# OECU_BASE4.net
KiCad netlist of a schematic drawn in Altium Designer
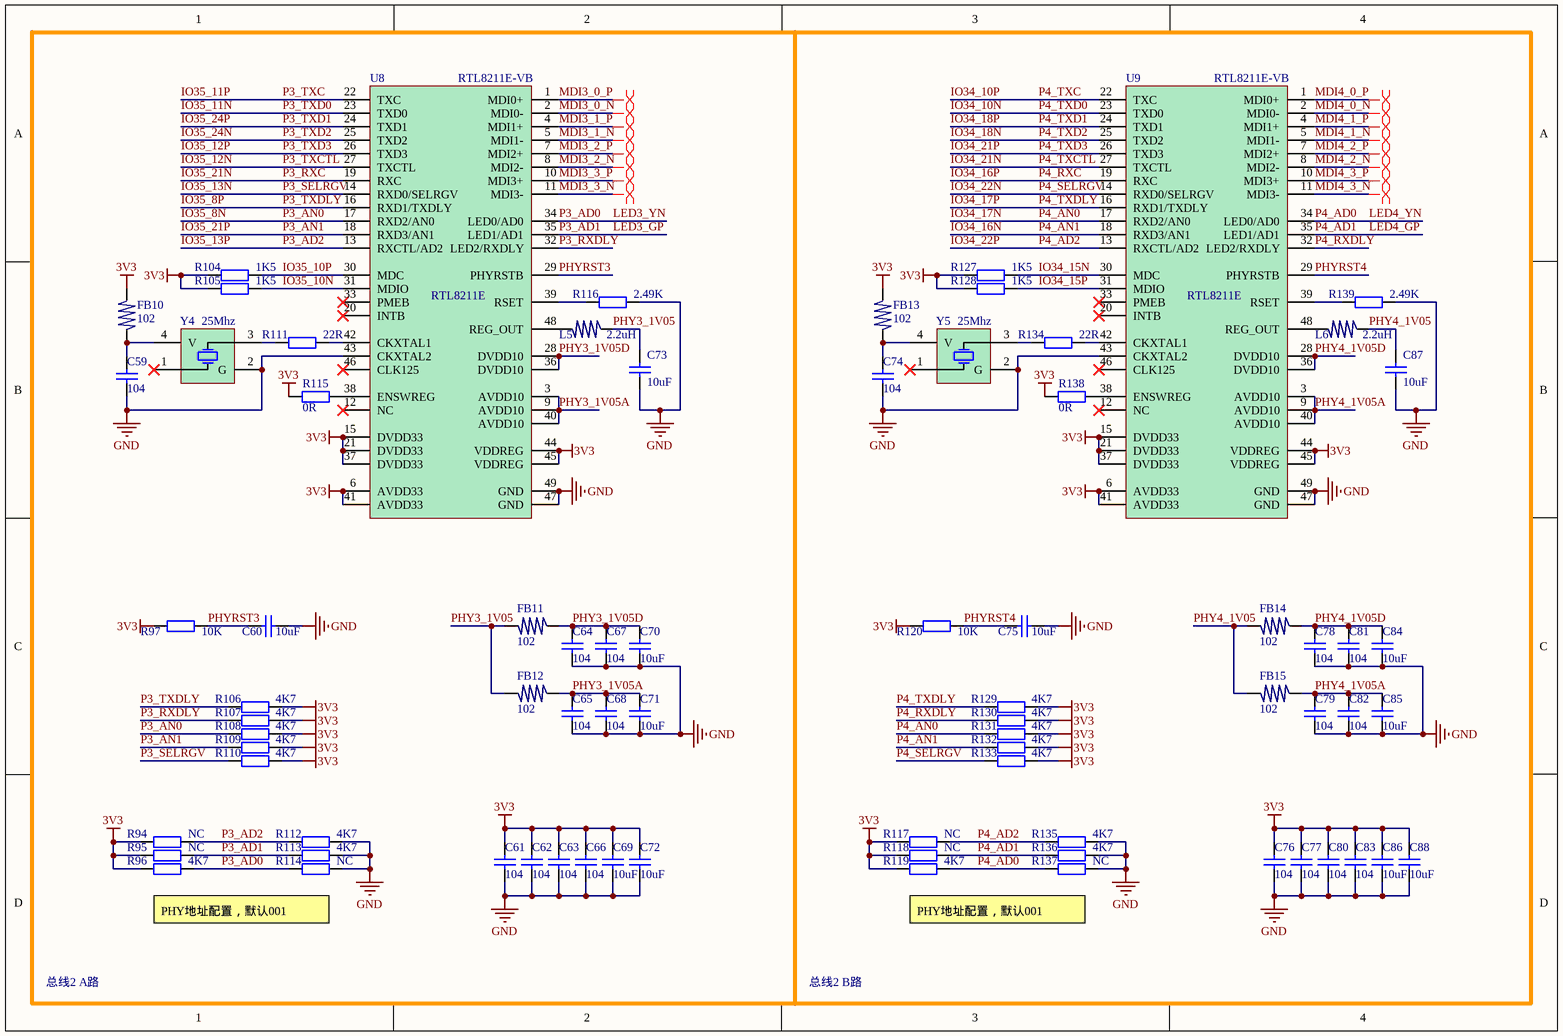
[diagram p0: OECU_BASE4.SchDoc]

(export (version "E")
  (design (tool "Eeschema 10.0.6"))
  (components
    (comp (ref "C59")
      (value "104")
      (footprint "0402")
      (description "贴片电容 0402")
      (libsource (lib "MT_Device") (part "CAP_0402"))
    )
    (comp (ref "C60")
      (value "10uF")
      (footprint "0402")
      (description "贴片电容 0402")
      (libsource (lib "MT_Device") (part "CAP_0402"))
    )
    (comp (ref "C61")
      (value "104")
      (footprint "0402")
      (description "贴片电容 0402")
      (libsource (lib "MT_Device") (part "CAP_0402"))
    )
    (comp (ref "C62")
      (value "104")
      (footprint "0402")
      (description "贴片电容 0402")
      (libsource (lib "MT_Device") (part "CAP_0402"))
    )
    (comp (ref "C63")
      (value "104")
      (footprint "0402")
      (description "贴片电容 0402")
      (libsource (lib "MT_Device") (part "CAP_0402"))
    )
    (comp (ref "C64")
      (value "104")
      (footprint "0402")
      (description "贴片电容 0402")
      (libsource (lib "MT_Device") (part "CAP_0402"))
    )
    (comp (ref "C65")
      (value "104")
      (footprint "0402")
      (description "贴片电容 0402")
      (libsource (lib "MT_Device") (part "CAP_0402"))
    )
    (comp (ref "C66")
      (value "104")
      (footprint "0402")
      (description "贴片电容 0402")
      (libsource (lib "MT_Device") (part "CAP_0402"))
    )
    (comp (ref "C67")
      (value "104")
      (footprint "0402")
      (description "贴片电容 0402")
      (libsource (lib "MT_Device") (part "CAP_0402"))
    )
    (comp (ref "C68")
      (value "104")
      (footprint "0402")
      (description "贴片电容 0402")
      (libsource (lib "MT_Device") (part "CAP_0402"))
    )
    (comp (ref "C69")
      (value "10uF")
      (footprint "0402")
      (description "贴片电容 0402")
      (libsource (lib "MT_Device") (part "CAP_0402"))
    )
    (comp (ref "C70")
      (value "10uF")
      (footprint "0402")
      (description "贴片电容 0402")
      (libsource (lib "MT_Device") (part "CAP_0402"))
    )
    (comp (ref "C71")
      (value "10uF")
      (footprint "0402")
      (description "贴片电容 0402")
      (libsource (lib "MT_Device") (part "CAP_0402"))
    )
    (comp (ref "C72")
      (value "10uF")
      (footprint "0402")
      (description "贴片电容 0402")
      (libsource (lib "MT_Device") (part "CAP_0402"))
    )
    (comp (ref "C73")
      (value "10uF")
      (footprint "0402")
      (description "贴片电容 0402")
      (libsource (lib "MT_Device") (part "CAP_0402"))
    )
    (comp (ref "C74")
      (value "104")
      (footprint "0402")
      (description "贴片电容 0402")
      (libsource (lib "MT_Device") (part "CAP_0402"))
    )
    (comp (ref "C75")
      (value "10uF")
      (footprint "0402")
      (description "贴片电容 0402")
      (libsource (lib "MT_Device") (part "CAP_0402"))
    )
    (comp (ref "C76")
      (value "104")
      (footprint "0402")
      (description "贴片电容 0402")
      (libsource (lib "MT_Device") (part "CAP_0402"))
    )
    (comp (ref "C77")
      (value "104")
      (footprint "0402")
      (description "贴片电容 0402")
      (libsource (lib "MT_Device") (part "CAP_0402"))
    )
    (comp (ref "C78")
      (value "104")
      (footprint "0402")
      (description "贴片电容 0402")
      (libsource (lib "MT_Device") (part "CAP_0402"))
    )
    (comp (ref "C79")
      (value "104")
      (footprint "0402")
      (description "贴片电容 0402")
      (libsource (lib "MT_Device") (part "CAP_0402"))
    )
    (comp (ref "C80")
      (value "104")
      (footprint "0402")
      (description "贴片电容 0402")
      (libsource (lib "MT_Device") (part "CAP_0402"))
    )
    (comp (ref "C81")
      (value "104")
      (footprint "0402")
      (description "贴片电容 0402")
      (libsource (lib "MT_Device") (part "CAP_0402"))
    )
    (comp (ref "C82")
      (value "104")
      (footprint "0402")
      (description "贴片电容 0402")
      (libsource (lib "MT_Device") (part "CAP_0402"))
    )
    (comp (ref "C83")
      (value "104")
      (footprint "0402")
      (description "贴片电容 0402")
      (libsource (lib "MT_Device") (part "CAP_0402"))
    )
    (comp (ref "C84")
      (value "10uF")
      (footprint "0402")
      (description "贴片电容 0402")
      (libsource (lib "MT_Device") (part "CAP_0402"))
    )
    (comp (ref "C85")
      (value "10uF")
      (footprint "0402")
      (description "贴片电容 0402")
      (libsource (lib "MT_Device") (part "CAP_0402"))
    )
    (comp (ref "C86")
      (value "10uF")
      (footprint "0402")
      (description "贴片电容 0402")
      (libsource (lib "MT_Device") (part "CAP_0402"))
    )
    (comp (ref "C87")
      (value "10uF")
      (footprint "0402")
      (description "贴片电容 0402")
      (libsource (lib "MT_Device") (part "CAP_0402"))
    )
    (comp (ref "C88")
      (value "10uF")
      (footprint "0402")
      (description "贴片电容 0402")
      (libsource (lib "MT_Device") (part "CAP_0402"))
    )
    (comp (ref "FB10")
      (value "102")
      (footprint "0402")
      (description "磁珠 0402")
      (libsource (lib "MT_Device") (part "FB_0402"))
    )
    (comp (ref "FB11")
      (value "102")
      (footprint "0603")
      (description "磁珠 0603")
      (libsource (lib "MT_Device") (part "FB_0603"))
    )
    (comp (ref "FB12")
      (value "102")
      (footprint "0603")
      (description "磁珠 0603")
      (libsource (lib "MT_Device") (part "FB_0603"))
    )
    (comp (ref "FB13")
      (value "102")
      (footprint "0402")
      (description "磁珠 0402")
      (libsource (lib "MT_Device") (part "FB_0402"))
    )
    (comp (ref "FB14")
      (value "102")
      (footprint "0603")
      (description "磁珠 0603")
      (libsource (lib "MT_Device") (part "FB_0603"))
    )
    (comp (ref "FB15")
      (value "102")
      (footprint "0603")
      (description "磁珠 0603")
      (libsource (lib "MT_Device") (part "FB_0603"))
    )
    (comp (ref "L5")
      (value "2.2uH")
      (footprint "0805")
      (description "电感 0805")
      (libsource (lib "MT_Device") (part "L_0805"))
    )
    (comp (ref "L6")
      (value "2.2uH")
      (footprint "0805")
      (description "电感 0805")
      (libsource (lib "MT_Device") (part "L_0805"))
    )
    (comp (ref "R94")
      (value "NC")
      (footprint "R_0402")
      (description "电阻 0402")
      (libsource (lib "MT_Device") (part "RES_0402"))
    )
    (comp (ref "R95")
      (value "NC")
      (footprint "R_0402")
      (description "电阻 0402")
      (libsource (lib "MT_Device") (part "RES_0402"))
    )
    (comp (ref "R96")
      (value "4K7")
      (footprint "R_0402")
      (description "电阻 0402")
      (libsource (lib "MT_Device") (part "RES_0402"))
    )
    (comp (ref "R97")
      (value "10K")
      (footprint "R_0402")
      (description "电阻 0402")
      (libsource (lib "MT_Device") (part "RES_0402"))
    )
    (comp (ref "R104")
      (value "1K5")
      (footprint "R_0402")
      (description "电阻 0402")
      (libsource (lib "") (part "RES_0402_1"))
    )
    (comp (ref "R105")
      (value "1K5")
      (footprint "R_0402")
      (description "电阻 0402")
      (libsource (lib "") (part "RES_0402_1"))
    )
    (comp (ref "R106")
      (value "4K7")
      (footprint "R_0402")
      (description "电阻 0402")
      (libsource (lib "MT_Device") (part "RES_0402"))
    )
    (comp (ref "R107")
      (value "4K7")
      (footprint "R_0402")
      (description "电阻 0402")
      (libsource (lib "MT_Device") (part "RES_0402"))
    )
    (comp (ref "R108")
      (value "4K7")
      (footprint "R_0402")
      (description "电阻 0402")
      (libsource (lib "MT_Device") (part "RES_0402"))
    )
    (comp (ref "R109")
      (value "4K7")
      (footprint "R_0402")
      (description "电阻 0402")
      (libsource (lib "MT_Device") (part "RES_0402"))
    )
    (comp (ref "R110")
      (value "4K7")
      (footprint "R_0402")
      (description "电阻 0402")
      (libsource (lib "MT_Device") (part "RES_0402"))
    )
    (comp (ref "R111")
      (value "22R")
      (footprint "R_0402")
      (description "电阻 0402")
      (libsource (lib "") (part "RES_0402_1"))
    )
    (comp (ref "R112")
      (value "4K7")
      (footprint "R_0402")
      (description "电阻 0402")
      (libsource (lib "MT_Device") (part "RES_0402"))
    )
    (comp (ref "R113")
      (value "4K7")
      (footprint "R_0402")
      (description "电阻 0402")
      (libsource (lib "MT_Device") (part "RES_0402"))
    )
    (comp (ref "R114")
      (value "NC")
      (footprint "R_0402")
      (description "电阻 0402")
      (libsource (lib "MT_Device") (part "RES_0402"))
    )
    (comp (ref "R115")
      (value "0R")
      (footprint "R_0402")
      (description "电阻 0402")
      (libsource (lib "") (part "RES_0402_1"))
    )
    (comp (ref "R116")
      (value "2.49K")
      (footprint "R_0402")
      (description "电阻 0402")
      (libsource (lib "MT_Device") (part "RES_0402"))
    )
    (comp (ref "R117")
      (value "NC")
      (footprint "R_0402")
      (description "电阻 0402")
      (libsource (lib "MT_Device") (part "RES_0402"))
    )
    (comp (ref "R118")
      (value "NC")
      (footprint "R_0402")
      (description "电阻 0402")
      (libsource (lib "MT_Device") (part "RES_0402"))
    )
    (comp (ref "R119")
      (value "4K7")
      (footprint "R_0402")
      (description "电阻 0402")
      (libsource (lib "MT_Device") (part "RES_0402"))
    )
    (comp (ref "R120")
      (value "10K")
      (footprint "R_0402")
      (description "电阻 0402")
      (libsource (lib "MT_Device") (part "RES_0402"))
    )
    (comp (ref "R127")
      (value "1K5")
      (footprint "R_0402")
      (description "电阻 0402")
      (libsource (lib "") (part "RES_0402_1"))
    )
    (comp (ref "R128")
      (value "1K5")
      (footprint "R_0402")
      (description "电阻 0402")
      (libsource (lib "") (part "RES_0402_1"))
    )
    (comp (ref "R129")
      (value "4K7")
      (footprint "R_0402")
      (description "电阻 0402")
      (libsource (lib "MT_Device") (part "RES_0402"))
    )
    (comp (ref "R130")
      (value "4K7")
      (footprint "R_0402")
      (description "电阻 0402")
      (libsource (lib "MT_Device") (part "RES_0402"))
    )
    (comp (ref "R131")
      (value "4K7")
      (footprint "R_0402")
      (description "电阻 0402")
      (libsource (lib "MT_Device") (part "RES_0402"))
    )
    (comp (ref "R132")
      (value "4K7")
      (footprint "R_0402")
      (description "电阻 0402")
      (libsource (lib "MT_Device") (part "RES_0402"))
    )
    (comp (ref "R133")
      (value "4K7")
      (footprint "R_0402")
      (description "电阻 0402")
      (libsource (lib "MT_Device") (part "RES_0402"))
    )
    (comp (ref "R134")
      (value "22R")
      (footprint "R_0402")
      (description "电阻 0402")
      (libsource (lib "") (part "RES_0402_1"))
    )
    (comp (ref "R135")
      (value "4K7")
      (footprint "R_0402")
      (description "电阻 0402")
      (libsource (lib "MT_Device") (part "RES_0402"))
    )
    (comp (ref "R136")
      (value "4K7")
      (footprint "R_0402")
      (description "电阻 0402")
      (libsource (lib "MT_Device") (part "RES_0402"))
    )
    (comp (ref "R137")
      (value "NC")
      (footprint "R_0402")
      (description "电阻 0402")
      (libsource (lib "MT_Device") (part "RES_0402"))
    )
    (comp (ref "R138")
      (value "0R")
      (footprint "R_0402")
      (description "电阻 0402")
      (libsource (lib "") (part "RES_0402_1"))
    )
    (comp (ref "R139")
      (value "2.49K")
      (footprint "R_0402")
      (description "电阻 0402")
      (libsource (lib "MT_Device") (part "RES_0402"))
    )
    (comp (ref "U8")
      (value "RTL8211E-VB")
      (footprint "QFN48")
      (description "QFN48")
      (libsource (lib "MT_Chip") (part "RTL8211E"))
    )
    (comp (ref "U9")
      (value "RTL8211E-VB")
      (footprint "QFN48")
      (description "QFN48")
      (libsource (lib "MT_Chip") (part "RTL8211E"))
    )
    (comp (ref "Y4") (value "25Mhz") (footprint "XTAL_3225") (libsource (lib "MT_Device") (part "XTAL_3225")))
    (comp (ref "Y5") (value "25Mhz") (footprint "XTAL_3225") (libsource (lib "MT_Device") (part "XTAL_3225")))
  )
  (nets
    (net (code "1") (name "/IO34_10N") (class "Default")
      (node (ref "U9") (pin "23") (pinfunction "TXD0_23") (pintype "passive"))
    )
    (net (code "2") (name "/IO34_10P") (class "Default")
      (node (ref "U9") (pin "22") (pinfunction "TXC_22") (pintype "passive"))
    )
    (net (code "3") (name "/IO34_15N") (class "Default")
      (node (ref "R127") (pin "1") (pinfunction "1_1") (pintype "passive"))
      (node (ref "U9") (pin "30") (pinfunction "MDC_30") (pintype "passive"))
    )
    (net (code "4") (name "/IO34_15P") (class "Default")
      (node (ref "R128") (pin "1") (pinfunction "1_1") (pintype "passive"))
      (node (ref "U9") (pin "31") (pinfunction "MDIO_31") (pintype "passive"))
    )
    (net (code "5") (name "/IO34_16N") (class "Default")
      (node (ref "R132") (pin "1") (pinfunction "1_1") (pintype "passive"))
      (node (ref "U9") (pin "18") (pinfunction "RXD3/AN1_18") (pintype "passive"))
    )
    (net (code "6") (name "/IO34_16P") (class "Default")
      (node (ref "U9") (pin "19") (pinfunction "RXC_19") (pintype "passive"))
    )
    (net (code "7") (name "/IO34_17N") (class "Default")
      (node (ref "R131") (pin "1") (pinfunction "1_1") (pintype "passive"))
      (node (ref "U9") (pin "17") (pinfunction "RXD2/AN0_17") (pintype "passive"))
    )
    (net (code "8") (name "/IO34_17P") (class "Default")
      (node (ref "R129") (pin "1") (pinfunction "1_1") (pintype "passive"))
      (node (ref "U9") (pin "16") (pinfunction "RXD1/TXDLY_16") (pintype "passive"))
    )
    (net (code "9") (name "/IO34_18N") (class "Default")
      (node (ref "U9") (pin "25") (pinfunction "TXD2_25") (pintype "passive"))
    )
    (net (code "10") (name "/IO34_18P") (class "Default")
      (node (ref "U9") (pin "24") (pinfunction "TXD1_24") (pintype "passive"))
    )
    (net (code "11") (name "/IO34_21N") (class "Default")
      (node (ref "U9") (pin "27") (pinfunction "TXCTL_27") (pintype "passive"))
    )
    (net (code "12") (name "/IO34_21P") (class "Default")
      (node (ref "U9") (pin "26") (pinfunction "TXD3_26") (pintype "passive"))
    )
    (net (code "13") (name "/IO34_22N") (class "Default")
      (node (ref "R133") (pin "1") (pinfunction "1_1") (pintype "passive"))
      (node (ref "U9") (pin "14") (pinfunction "RXD0/SELRGV_14") (pintype "passive"))
    )
    (net (code "14") (name "/IO34_22P") (class "Default")
      (node (ref "R117") (pin "2") (pinfunction "2_2") (pintype "passive"))
      (node (ref "R135") (pin "1") (pinfunction "1_1") (pintype "passive"))
      (node (ref "U9") (pin "13") (pinfunction "RXCTL/AD2_13") (pintype "passive"))
    )
    (net (code "15") (name "/IO35_8N") (class "Default")
      (node (ref "R108") (pin "1") (pinfunction "1_1") (pintype "passive"))
      (node (ref "U8") (pin "17") (pinfunction "RXD2/AN0_17") (pintype "passive"))
    )
    (net (code "16") (name "/IO35_8P") (class "Default")
      (node (ref "R106") (pin "1") (pinfunction "1_1") (pintype "passive"))
      (node (ref "U8") (pin "16") (pinfunction "RXD1/TXDLY_16") (pintype "passive"))
    )
    (net (code "17") (name "/IO35_10N") (class "Default")
      (node (ref "R105") (pin "1") (pinfunction "1_1") (pintype "passive"))
      (node (ref "U8") (pin "31") (pinfunction "MDIO_31") (pintype "passive"))
    )
    (net (code "18") (name "/IO35_10P") (class "Default")
      (node (ref "R104") (pin "1") (pinfunction "1_1") (pintype "passive"))
      (node (ref "U8") (pin "30") (pinfunction "MDC_30") (pintype "passive"))
    )
    (net (code "19") (name "/IO35_11N") (class "Default")
      (node (ref "U8") (pin "23") (pinfunction "TXD0_23") (pintype "passive"))
    )
    (net (code "20") (name "/IO35_11P") (class "Default")
      (node (ref "U8") (pin "22") (pinfunction "TXC_22") (pintype "passive"))
    )
    (net (code "21") (name "/IO35_12N") (class "Default")
      (node (ref "U8") (pin "27") (pinfunction "TXCTL_27") (pintype "passive"))
    )
    (net (code "22") (name "/IO35_12P") (class "Default")
      (node (ref "U8") (pin "26") (pinfunction "TXD3_26") (pintype "passive"))
    )
    (net (code "23") (name "/IO35_13N") (class "Default")
      (node (ref "R110") (pin "1") (pinfunction "1_1") (pintype "passive"))
      (node (ref "U8") (pin "14") (pinfunction "RXD0/SELRGV_14") (pintype "passive"))
    )
    (net (code "24") (name "/IO35_13P") (class "Default")
      (node (ref "R112") (pin "1") (pinfunction "1_1") (pintype "passive"))
      (node (ref "R94") (pin "2") (pinfunction "2_2") (pintype "passive"))
      (node (ref "U8") (pin "13") (pinfunction "RXCTL/AD2_13") (pintype "passive"))
    )
    (net (code "25") (name "/IO35_21N") (class "Default")
      (node (ref "U8") (pin "19") (pinfunction "RXC_19") (pintype "passive"))
    )
    (net (code "26") (name "/IO35_21P") (class "Default")
      (node (ref "R109") (pin "1") (pinfunction "1_1") (pintype "passive"))
      (node (ref "U8") (pin "18") (pinfunction "RXD3/AN1_18") (pintype "passive"))
    )
    (net (code "27") (name "/IO35_24N") (class "Default")
      (node (ref "U8") (pin "25") (pinfunction "TXD2_25") (pintype "passive"))
    )
    (net (code "28") (name "/IO35_24P") (class "Default")
      (node (ref "U8") (pin "24") (pinfunction "TXD1_24") (pintype "passive"))
    )
    (net (code "29") (name "/LED3_GP") (class "Default")
      (node (ref "R113") (pin "1") (pinfunction "1_1") (pintype "passive"))
      (node (ref "R95") (pin "2") (pinfunction "2_2") (pintype "passive"))
      (node (ref "U8") (pin "35") (pinfunction "LED1/AD1_35") (pintype "passive"))
    )
    (net (code "30") (name "/LED3_YN") (class "Default")
      (node (ref "R114") (pin "1") (pinfunction "1_1") (pintype "passive"))
      (node (ref "R96") (pin "2") (pinfunction "2_2") (pintype "passive"))
      (node (ref "U8") (pin "34") (pinfunction "LED0/AD0_34") (pintype "passive"))
    )
    (net (code "31") (name "/LED4_GP") (class "Default")
      (node (ref "R118") (pin "2") (pinfunction "2_2") (pintype "passive"))
      (node (ref "R136") (pin "1") (pinfunction "1_1") (pintype "passive"))
      (node (ref "U9") (pin "35") (pinfunction "LED1/AD1_35") (pintype "passive"))
    )
    (net (code "32") (name "/LED4_YN") (class "Default")
      (node (ref "R119") (pin "2") (pinfunction "2_2") (pintype "passive"))
      (node (ref "R137") (pin "1") (pinfunction "1_1") (pintype "passive"))
      (node (ref "U9") (pin "34") (pinfunction "LED0/AD0_34") (pintype "passive"))
    )
    (net (code "33") (name "/MDI3_0_N") (class "Default")
      (node (ref "U8") (pin "2") (pinfunction "MDI0-_2") (pintype "passive"))
    )
    (net (code "34") (name "/MDI3_0_P") (class "Default")
      (node (ref "U8") (pin "1") (pinfunction "MDI0+_1") (pintype "passive"))
    )
    (net (code "35") (name "/MDI3_1_N") (class "Default")
      (node (ref "U8") (pin "5") (pinfunction "MDI1-_5") (pintype "passive"))
    )
    (net (code "36") (name "/MDI3_1_P") (class "Default")
      (node (ref "U8") (pin "4") (pinfunction "MDI1+_4") (pintype "passive"))
    )
    (net (code "37") (name "/MDI3_2_N") (class "Default")
      (node (ref "U8") (pin "8") (pinfunction "MDI2-_8") (pintype "passive"))
    )
    (net (code "38") (name "/MDI3_2_P") (class "Default")
      (node (ref "U8") (pin "7") (pinfunction "MDI2+_7") (pintype "passive"))
    )
    (net (code "39") (name "/MDI3_3_N") (class "Default")
      (node (ref "U8") (pin "11") (pinfunction "MDI3-_11") (pintype "passive"))
    )
    (net (code "40") (name "/MDI3_3_P") (class "Default")
      (node (ref "U8") (pin "10") (pinfunction "MDI3+_10") (pintype "passive"))
    )
    (net (code "41") (name "/MDI4_0_N") (class "Default")
      (node (ref "U9") (pin "2") (pinfunction "MDI0-_2") (pintype "passive"))
    )
    (net (code "42") (name "/MDI4_0_P") (class "Default")
      (node (ref "U9") (pin "1") (pinfunction "MDI0+_1") (pintype "passive"))
    )
    (net (code "43") (name "/MDI4_1_N") (class "Default")
      (node (ref "U9") (pin "5") (pinfunction "MDI1-_5") (pintype "passive"))
    )
    (net (code "44") (name "/MDI4_1_P") (class "Default")
      (node (ref "U9") (pin "4") (pinfunction "MDI1+_4") (pintype "passive"))
    )
    (net (code "45") (name "/MDI4_2_N") (class "Default")
      (node (ref "U9") (pin "8") (pinfunction "MDI2-_8") (pintype "passive"))
    )
    (net (code "46") (name "/MDI4_2_P") (class "Default")
      (node (ref "U9") (pin "7") (pinfunction "MDI2+_7") (pintype "passive"))
    )
    (net (code "47") (name "/MDI4_3_N") (class "Default")
      (node (ref "U9") (pin "11") (pinfunction "MDI3-_11") (pintype "passive"))
    )
    (net (code "48") (name "/MDI4_3_P") (class "Default")
      (node (ref "U9") (pin "10") (pinfunction "MDI3+_10") (pintype "passive"))
    )
    (net (code "49") (name "/P3_RXDLY") (class "Default")
      (node (ref "R107") (pin "1") (pinfunction "1_1") (pintype "passive"))
      (node (ref "U8") (pin "32") (pinfunction "LED2/RXDLY_32") (pintype "passive"))
    )
    (net (code "50") (name "/P4_RXDLY") (class "Default")
      (node (ref "R130") (pin "1") (pinfunction "1_1") (pintype "passive"))
      (node (ref "U9") (pin "32") (pinfunction "LED2/RXDLY_32") (pintype "passive"))
    )
    (net (code "51") (name "/PHY3_1V05") (class "Default")
      (node (ref "C73") (pin "2") (pinfunction "2_2") (pintype "passive"))
      (node (ref "FB11") (pin "1") (pintype "passive"))
      (node (ref "FB12") (pin "1") (pintype "passive"))
      (node (ref "L5") (pin "1") (pintype "passive"))
    )
    (net (code "52") (name "/PHY3_1V05A") (class "Default")
      (node (ref "C65") (pin "2") (pinfunction "2_2") (pintype "passive"))
      (node (ref "C68") (pin "2") (pinfunction "2_2") (pintype "passive"))
      (node (ref "C71") (pin "2") (pinfunction "2_2") (pintype "passive"))
      (node (ref "FB12") (pin "2") (pintype "passive"))
      (node (ref "U8") (pin "3") (pinfunction "AVDD10_3") (pintype "passive"))
      (node (ref "U8") (pin "40") (pinfunction "AVDD10_40") (pintype "passive"))
      (node (ref "U8") (pin "9") (pinfunction "AVDD10_9") (pintype "passive"))
    )
    (net (code "53") (name "/PHY3_1V05D") (class "Default")
      (node (ref "C64") (pin "2") (pinfunction "2_2") (pintype "passive"))
      (node (ref "C67") (pin "2") (pinfunction "2_2") (pintype "passive"))
      (node (ref "C70") (pin "2") (pinfunction "2_2") (pintype "passive"))
      (node (ref "FB11") (pin "2") (pintype "passive"))
      (node (ref "U8") (pin "28") (pinfunction "DVDD10_28") (pintype "passive"))
      (node (ref "U8") (pin "36") (pinfunction "DVDD10_36") (pintype "passive"))
    )
    (net (code "54") (name "/PHY4_1V05") (class "Default")
      (node (ref "C87") (pin "2") (pinfunction "2_2") (pintype "passive"))
      (node (ref "FB14") (pin "1") (pintype "passive"))
      (node (ref "FB15") (pin "1") (pintype "passive"))
      (node (ref "L6") (pin "1") (pintype "passive"))
    )
    (net (code "55") (name "/PHY4_1V05A") (class "Default")
      (node (ref "C79") (pin "2") (pinfunction "2_2") (pintype "passive"))
      (node (ref "C82") (pin "2") (pinfunction "2_2") (pintype "passive"))
      (node (ref "C85") (pin "2") (pinfunction "2_2") (pintype "passive"))
      (node (ref "FB15") (pin "2") (pintype "passive"))
      (node (ref "U9") (pin "3") (pinfunction "AVDD10_3") (pintype "passive"))
      (node (ref "U9") (pin "40") (pinfunction "AVDD10_40") (pintype "passive"))
      (node (ref "U9") (pin "9") (pinfunction "AVDD10_9") (pintype "passive"))
    )
    (net (code "56") (name "/PHY4_1V05D") (class "Default")
      (node (ref "C78") (pin "2") (pinfunction "2_2") (pintype "passive"))
      (node (ref "C81") (pin "2") (pinfunction "2_2") (pintype "passive"))
      (node (ref "C84") (pin "2") (pinfunction "2_2") (pintype "passive"))
      (node (ref "FB14") (pin "2") (pintype "passive"))
      (node (ref "U9") (pin "28") (pinfunction "DVDD10_28") (pintype "passive"))
      (node (ref "U9") (pin "36") (pinfunction "DVDD10_36") (pintype "passive"))
    )
    (net (code "57") (name "/PHYRST3") (class "Default")
      (node (ref "C60") (pin "1") (pinfunction "1_1") (pintype "passive"))
      (node (ref "R97") (pin "2") (pinfunction "2_2") (pintype "passive"))
      (node (ref "U8") (pin "29") (pinfunction "PHYRSTB_29") (pintype "passive"))
    )
    (net (code "58") (name "/PHYRST4") (class "Default")
      (node (ref "C75") (pin "1") (pinfunction "1_1") (pintype "passive"))
      (node (ref "R120") (pin "2") (pinfunction "2_2") (pintype "passive"))
      (node (ref "U9") (pin "29") (pinfunction "PHYRSTB_29") (pintype "passive"))
    )
    (net (code "59") (name "3V3") (class "Default")
      (node (ref "C61") (pin "1") (pinfunction "1_1") (pintype "passive"))
      (node (ref "C62") (pin "1") (pinfunction "1_1") (pintype "passive"))
      (node (ref "C63") (pin "1") (pinfunction "1_1") (pintype "passive"))
      (node (ref "C66") (pin "1") (pinfunction "1_1") (pintype "passive"))
      (node (ref "C69") (pin "1") (pinfunction "1_1") (pintype "passive"))
      (node (ref "C72") (pin "1") (pinfunction "1_1") (pintype "passive"))
      (node (ref "C76") (pin "1") (pinfunction "1_1") (pintype "passive"))
      (node (ref "C77") (pin "1") (pinfunction "1_1") (pintype "passive"))
      (node (ref "C80") (pin "1") (pinfunction "1_1") (pintype "passive"))
      (node (ref "C83") (pin "1") (pinfunction "1_1") (pintype "passive"))
      (node (ref "C86") (pin "1") (pinfunction "1_1") (pintype "passive"))
      (node (ref "C88") (pin "1") (pinfunction "1_1") (pintype "passive"))
      (node (ref "FB10") (pin "2") (pintype "passive"))
      (node (ref "FB13") (pin "2") (pintype "passive"))
      (node (ref "R104") (pin "2") (pinfunction "2_2") (pintype "passive"))
      (node (ref "R105") (pin "2") (pinfunction "2_2") (pintype "passive"))
      (node (ref "R106") (pin "2") (pinfunction "2_2") (pintype "passive"))
      (node (ref "R107") (pin "2") (pinfunction "2_2") (pintype "passive"))
      (node (ref "R108") (pin "2") (pinfunction "2_2") (pintype "passive"))
      (node (ref "R109") (pin "2") (pinfunction "2_2") (pintype "passive"))
      (node (ref "R110") (pin "2") (pinfunction "2_2") (pintype "passive"))
      (node (ref "R115") (pin "2") (pinfunction "2_2") (pintype "passive"))
      (node (ref "R117") (pin "1") (pinfunction "1_1") (pintype "passive"))
      (node (ref "R118") (pin "1") (pinfunction "1_1") (pintype "passive"))
      (node (ref "R119") (pin "1") (pinfunction "1_1") (pintype "passive"))
      (node (ref "R120") (pin "1") (pinfunction "1_1") (pintype "passive"))
      (node (ref "R127") (pin "2") (pinfunction "2_2") (pintype "passive"))
      (node (ref "R128") (pin "2") (pinfunction "2_2") (pintype "passive"))
      (node (ref "R129") (pin "2") (pinfunction "2_2") (pintype "passive"))
      (node (ref "R130") (pin "2") (pinfunction "2_2") (pintype "passive"))
      (node (ref "R131") (pin "2") (pinfunction "2_2") (pintype "passive"))
      (node (ref "R132") (pin "2") (pinfunction "2_2") (pintype "passive"))
      (node (ref "R133") (pin "2") (pinfunction "2_2") (pintype "passive"))
      (node (ref "R138") (pin "2") (pinfunction "2_2") (pintype "passive"))
      (node (ref "R94") (pin "1") (pinfunction "1_1") (pintype "passive"))
      (node (ref "R95") (pin "1") (pinfunction "1_1") (pintype "passive"))
      (node (ref "R96") (pin "1") (pinfunction "1_1") (pintype "passive"))
      (node (ref "R97") (pin "1") (pinfunction "1_1") (pintype "passive"))
      (node (ref "U8") (pin "15") (pinfunction "DVDD33_15") (pintype "passive"))
      (node (ref "U8") (pin "21") (pinfunction "DVDD33_21") (pintype "passive"))
      (node (ref "U8") (pin "37") (pinfunction "DVDD33_37") (pintype "passive"))
      (node (ref "U8") (pin "41") (pinfunction "AVDD33_41") (pintype "passive"))
      (node (ref "U8") (pin "44") (pinfunction "VDDREG_44") (pintype "passive"))
      (node (ref "U8") (pin "45") (pinfunction "VDDREG_45") (pintype "passive"))
      (node (ref "U8") (pin "6") (pinfunction "AVDD33_6") (pintype "passive"))
      (node (ref "U9") (pin "15") (pinfunction "DVDD33_15") (pintype "passive"))
      (node (ref "U9") (pin "21") (pinfunction "DVDD33_21") (pintype "passive"))
      (node (ref "U9") (pin "37") (pinfunction "DVDD33_37") (pintype "passive"))
      (node (ref "U9") (pin "41") (pinfunction "AVDD33_41") (pintype "passive"))
      (node (ref "U9") (pin "44") (pinfunction "VDDREG_44") (pintype "passive"))
      (node (ref "U9") (pin "45") (pinfunction "VDDREG_45") (pintype "passive"))
      (node (ref "U9") (pin "6") (pinfunction "AVDD33_6") (pintype "passive"))
    )
    (net (code "60") (name "GND") (class "Default")
      (node (ref "C59") (pin "1") (pinfunction "1_1") (pintype "passive"))
      (node (ref "C60") (pin "2") (pinfunction "2_2") (pintype "passive"))
      (node (ref "C61") (pin "2") (pinfunction "2_2") (pintype "passive"))
      (node (ref "C62") (pin "2") (pinfunction "2_2") (pintype "passive"))
      (node (ref "C63") (pin "2") (pinfunction "2_2") (pintype "passive"))
      (node (ref "C64") (pin "1") (pinfunction "1_1") (pintype "passive"))
      (node (ref "C65") (pin "1") (pinfunction "1_1") (pintype "passive"))
      (node (ref "C66") (pin "2") (pinfunction "2_2") (pintype "passive"))
      (node (ref "C67") (pin "1") (pinfunction "1_1") (pintype "passive"))
      (node (ref "C68") (pin "1") (pinfunction "1_1") (pintype "passive"))
      (node (ref "C69") (pin "2") (pinfunction "2_2") (pintype "passive"))
      (node (ref "C70") (pin "1") (pinfunction "1_1") (pintype "passive"))
      (node (ref "C71") (pin "1") (pinfunction "1_1") (pintype "passive"))
      (node (ref "C72") (pin "2") (pinfunction "2_2") (pintype "passive"))
      (node (ref "C73") (pin "1") (pinfunction "1_1") (pintype "passive"))
      (node (ref "C74") (pin "1") (pinfunction "1_1") (pintype "passive"))
      (node (ref "C75") (pin "2") (pinfunction "2_2") (pintype "passive"))
      (node (ref "C76") (pin "2") (pinfunction "2_2") (pintype "passive"))
      (node (ref "C77") (pin "2") (pinfunction "2_2") (pintype "passive"))
      (node (ref "C78") (pin "1") (pinfunction "1_1") (pintype "passive"))
      (node (ref "C79") (pin "1") (pinfunction "1_1") (pintype "passive"))
      (node (ref "C80") (pin "2") (pinfunction "2_2") (pintype "passive"))
      (node (ref "C81") (pin "1") (pinfunction "1_1") (pintype "passive"))
      (node (ref "C82") (pin "1") (pinfunction "1_1") (pintype "passive"))
      (node (ref "C83") (pin "2") (pinfunction "2_2") (pintype "passive"))
      (node (ref "C84") (pin "1") (pinfunction "1_1") (pintype "passive"))
      (node (ref "C85") (pin "1") (pinfunction "1_1") (pintype "passive"))
      (node (ref "C86") (pin "2") (pinfunction "2_2") (pintype "passive"))
      (node (ref "C87") (pin "1") (pinfunction "1_1") (pintype "passive"))
      (node (ref "C88") (pin "2") (pinfunction "2_2") (pintype "passive"))
      (node (ref "R112") (pin "2") (pinfunction "2_2") (pintype "passive"))
      (node (ref "R113") (pin "2") (pinfunction "2_2") (pintype "passive"))
      (node (ref "R114") (pin "2") (pinfunction "2_2") (pintype "passive"))
      (node (ref "R116") (pin "2") (pinfunction "2_2") (pintype "passive"))
      (node (ref "R135") (pin "2") (pinfunction "2_2") (pintype "passive"))
      (node (ref "R136") (pin "2") (pinfunction "2_2") (pintype "passive"))
      (node (ref "R137") (pin "2") (pinfunction "2_2") (pintype "passive"))
      (node (ref "R139") (pin "2") (pinfunction "2_2") (pintype "passive"))
      (node (ref "U8") (pin "43") (pinfunction "CKXTAL2_43") (pintype "passive"))
      (node (ref "U8") (pin "47") (pinfunction "GND_47") (pintype "passive"))
      (node (ref "U8") (pin "49") (pinfunction "GND_49") (pintype "passive"))
      (node (ref "U9") (pin "43") (pinfunction "CKXTAL2_43") (pintype "passive"))
      (node (ref "U9") (pin "47") (pinfunction "GND_47") (pintype "passive"))
      (node (ref "U9") (pin "49") (pinfunction "GND_49") (pintype "passive"))
      (node (ref "Y4") (pin "2") (pinfunction "G_2") (pintype "passive"))
      (node (ref "Y5") (pin "2") (pinfunction "G_2") (pintype "passive"))
    )
    (net (code "61") (name "Net-(U8-CKXTAL1)") (class "Default")
      (node (ref "R111") (pin "1") (pinfunction "1_1") (pintype "passive"))
      (node (ref "U8") (pin "42") (pinfunction "CKXTAL1_42") (pintype "passive"))
    )
    (net (code "62") (name "Net-(U8-ENSWREG)") (class "Default")
      (node (ref "R115") (pin "1") (pinfunction "1_1") (pintype "passive"))
      (node (ref "U8") (pin "38") (pinfunction "ENSWREG_38") (pintype "passive"))
    )
    (net (code "63") (name "Net-(U8-REG_OUT)") (class "Default")
      (node (ref "L5") (pin "2") (pintype "passive"))
      (node (ref "U8") (pin "48") (pinfunction "REG_OUT_48") (pintype "passive"))
    )
    (net (code "64") (name "Net-(U8-RSET)") (class "Default")
      (node (ref "R116") (pin "1") (pinfunction "1_1") (pintype "passive"))
      (node (ref "U8") (pin "39") (pinfunction "RSET_39") (pintype "passive"))
    )
    (net (code "65") (name "Net-(U9-CKXTAL1)") (class "Default")
      (node (ref "R134") (pin "1") (pinfunction "1_1") (pintype "passive"))
      (node (ref "U9") (pin "42") (pinfunction "CKXTAL1_42") (pintype "passive"))
    )
    (net (code "66") (name "Net-(U9-ENSWREG)") (class "Default")
      (node (ref "R138") (pin "1") (pinfunction "1_1") (pintype "passive"))
      (node (ref "U9") (pin "38") (pinfunction "ENSWREG_38") (pintype "passive"))
    )
    (net (code "67") (name "Net-(U9-REG_OUT)") (class "Default")
      (node (ref "L6") (pin "2") (pintype "passive"))
      (node (ref "U9") (pin "48") (pinfunction "REG_OUT_48") (pintype "passive"))
    )
    (net (code "68") (name "Net-(U9-RSET)") (class "Default")
      (node (ref "R139") (pin "1") (pinfunction "1_1") (pintype "passive"))
      (node (ref "U9") (pin "39") (pinfunction "RSET_39") (pintype "passive"))
    )
    (net (code "69") (name "Net-(Y4-OP)") (class "Default")
      (node (ref "R111") (pin "2") (pinfunction "2_2") (pintype "passive"))
      (node (ref "Y4") (pin "3") (pinfunction "OP_3") (pintype "passive"))
    )
    (net (code "70") (name "Net-(Y4-V)") (class "Default")
      (node (ref "C59") (pin "2") (pinfunction "2_2") (pintype "passive"))
      (node (ref "FB10") (pin "1") (pintype "passive"))
      (node (ref "Y4") (pin "4") (pinfunction "V_4") (pintype "passive"))
    )
    (net (code "71") (name "Net-(Y5-OP)") (class "Default")
      (node (ref "R134") (pin "2") (pinfunction "2_2") (pintype "passive"))
      (node (ref "Y5") (pin "3") (pinfunction "OP_3") (pintype "passive"))
    )
    (net (code "72") (name "Net-(Y5-V)") (class "Default")
      (node (ref "C74") (pin "2") (pinfunction "2_2") (pintype "passive"))
      (node (ref "FB13") (pin "1") (pintype "passive"))
      (node (ref "Y5") (pin "4") (pinfunction "V_4") (pintype "passive"))
    )
    (net (code "73") (name "unconnected-(U8-CLK125-Pad46)") (class "Default")
      (node (ref "U8") (pin "46") (pinfunction "CLK125_46") (pintype "passive+no_connect"))
    )
    (net (code "74") (name "unconnected-(U8-INTB-Pad20)") (class "Default")
      (node (ref "U8") (pin "20") (pinfunction "INTB_20") (pintype "passive+no_connect"))
    )
    (net (code "75") (name "unconnected-(U8-NC-Pad12)") (class "Default")
      (node (ref "U8") (pin "12") (pinfunction "NC_12") (pintype "passive+no_connect"))
    )
    (net (code "76") (name "unconnected-(U8-PMEB-Pad33)") (class "Default")
      (node (ref "U8") (pin "33") (pinfunction "PMEB_33") (pintype "passive+no_connect"))
    )
    (net (code "77") (name "unconnected-(U9-CLK125-Pad46)") (class "Default")
      (node (ref "U9") (pin "46") (pinfunction "CLK125_46") (pintype "passive+no_connect"))
    )
    (net (code "78") (name "unconnected-(U9-INTB-Pad20)") (class "Default")
      (node (ref "U9") (pin "20") (pinfunction "INTB_20") (pintype "passive+no_connect"))
    )
    (net (code "79") (name "unconnected-(U9-NC-Pad12)") (class "Default")
      (node (ref "U9") (pin "12") (pinfunction "NC_12") (pintype "passive+no_connect"))
    )
    (net (code "80") (name "unconnected-(U9-PMEB-Pad33)") (class "Default")
      (node (ref "U9") (pin "33") (pinfunction "PMEB_33") (pintype "passive+no_connect"))
    )
    (net (code "81") (name "unconnected-(Y4-EC-Pad1)") (class "Default")
      (node (ref "Y4") (pin "1") (pinfunction "EC_1") (pintype "passive+no_connect"))
    )
    (net (code "82") (name "unconnected-(Y5-EC-Pad1)") (class "Default")
      (node (ref "Y5") (pin "1") (pinfunction "EC_1") (pintype "passive+no_connect"))
    )
  )
)
